# Arduino_Nano_Potentiometers.net
KiCad netlist of a schematic drawn in Altium Designer
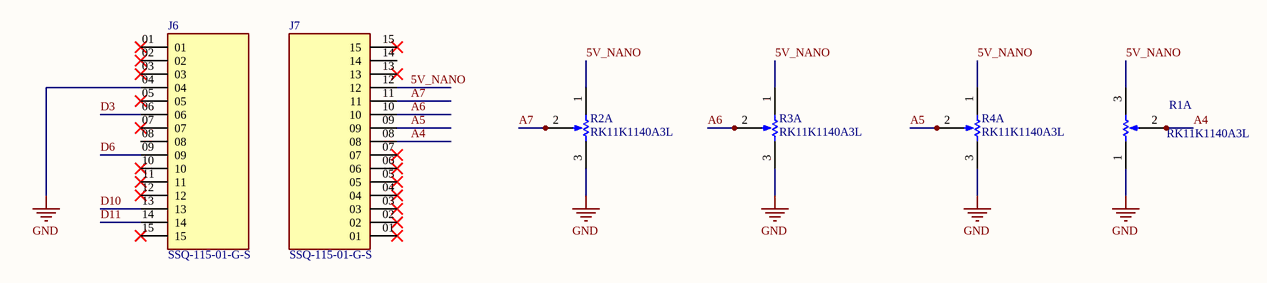
[diagram p0: Arduino_Nano + Potentiometers.schDoc]

(export (version "E")
  (design (tool "Eeschema 10.0.6"))
  (components
    (comp (ref "J6")
      (value "SSQ-115-01-G-S")
      (footprint "PcbLib1:SAMTEC_SSQ-115-01-G-S")
      (fields (field (name "MF") "Samtec"))
      (libsource (lib "") (part "SSQ-115-01-G-S_1"))
    )
    (comp (ref "J7")
      (value "SSQ-115-01-G-S")
      (footprint "PcbLib1:SAMTEC_SSQ-115-01-G-S")
      (fields (field (name "MF") "Samtec"))
      (libsource (lib "Schlib1") (part "SSQ-115-01-G-S"))
    )
    (comp (ref "R1")
      (value "RK11K1140A3L")
      (footprint "ALPS-RK11K1140A3L_V")
      (description "Rotary Potentiometer, 0.05 W, -10 to 70 degC, 4-Pin THD, RoHS")
      (fields (field (name "MANUFACTURER") "ALPS") (field (name "TOLERANCE") "20%"))
      (libsource (lib "") (part "CMP-2000-06982-1_1"))
    )
    (comp (ref "R2")
      (value "RK11K1140A3L")
      (footprint "ALPS-RK11K1140A3L_V")
      (description "Rotary Potentiometer, 0.05 W, -10 to 70 degC, 4-Pin THD, RoHS")
      (fields (field (name "MANUFACTURER") "ALPS") (field (name "TOLERANCE") "20%"))
      (libsource (lib "Schlib1") (part "CMP-2000-06982-1"))
    )
    (comp (ref "R3")
      (value "RK11K1140A3L")
      (footprint "ALPS-RK11K1140A3L_V")
      (description "Rotary Potentiometer, 0.05 W, -10 to 70 degC, 4-Pin THD, RoHS")
      (fields (field (name "MANUFACTURER") "ALPS") (field (name "TOLERANCE") "20%"))
      (libsource (lib "Schlib1") (part "CMP-2000-06982-1"))
    )
    (comp (ref "R4")
      (value "RK11K1140A3L")
      (footprint "ALPS-RK11K1140A3L_V")
      (description "Rotary Potentiometer, 0.05 W, -10 to 70 degC, 4-Pin THD, RoHS")
      (fields (field (name "MANUFACTURER") "ALPS") (field (name "TOLERANCE") "20%"))
      (libsource (lib "Schlib1") (part "CMP-2000-06982-1"))
    )
  )
  (nets
    (net (code "1") (name "/5V_NANO") (class "Default")
      (node (ref "J7") (pin "12") (pinfunction "12_12") (pintype "passive"))
      (node (ref "R1") (pin "3") (pinfunction "CW_3") (pintype "passive"))
      (node (ref "R2") (pin "1") (pinfunction "CCW_1") (pintype "passive"))
      (node (ref "R3") (pin "1") (pinfunction "CCW_1") (pintype "passive"))
      (node (ref "R4") (pin "1") (pinfunction "CCW_1") (pintype "passive"))
    )
    (net (code "2") (name "/A4") (class "Default")
      (node (ref "J7") (pin "08") (pinfunction "08_08") (pintype "passive"))
      (node (ref "R1") (pin "2") (pinfunction "WIPER_2") (pintype "passive"))
    )
    (net (code "3") (name "/A5") (class "Default")
      (node (ref "J7") (pin "09") (pinfunction "09_09") (pintype "passive"))
      (node (ref "R4") (pin "2") (pinfunction "WIPER_2") (pintype "passive"))
    )
    (net (code "4") (name "/A6") (class "Default")
      (node (ref "J7") (pin "10") (pinfunction "10_10") (pintype "passive"))
      (node (ref "R3") (pin "2") (pinfunction "WIPER_2") (pintype "passive"))
    )
    (net (code "5") (name "/A7") (class "Default")
      (node (ref "J7") (pin "11") (pinfunction "11_11") (pintype "passive"))
      (node (ref "R2") (pin "2") (pinfunction "WIPER_2") (pintype "passive"))
    )
    (net (code "6") (name "/D3") (class "Default")
      (node (ref "J6") (pin "06") (pinfunction "06_06") (pintype "passive"))
    )
    (net (code "7") (name "/D6") (class "Default")
      (node (ref "J6") (pin "09") (pinfunction "09_09") (pintype "passive"))
    )
    (net (code "8") (name "/D10") (class "Default")
      (node (ref "J6") (pin "13") (pinfunction "13_13") (pintype "passive"))
    )
    (net (code "9") (name "/D11") (class "Default")
      (node (ref "J6") (pin "14") (pinfunction "14_14") (pintype "passive"))
    )
    (net (code "10") (name "GND") (class "Default")
      (node (ref "J6") (pin "04") (pinfunction "04_04") (pintype "passive"))
      (node (ref "R1") (pin "1") (pinfunction "CCW_1") (pintype "passive"))
      (node (ref "R2") (pin "3") (pinfunction "CW_3") (pintype "passive"))
      (node (ref "R3") (pin "3") (pinfunction "CW_3") (pintype "passive"))
      (node (ref "R4") (pin "3") (pinfunction "CW_3") (pintype "passive"))
    )
    (net (code "11") (name "unconnected-(J6-Pad01)") (class "Default")
      (node (ref "J6") (pin "01") (pinfunction "01_01") (pintype "passive+no_connect"))
    )
    (net (code "12") (name "unconnected-(J6-Pad02)") (class "Default")
      (node (ref "J6") (pin "02") (pinfunction "02_02") (pintype "passive+no_connect"))
    )
    (net (code "13") (name "unconnected-(J6-Pad03)") (class "Default")
      (node (ref "J6") (pin "03") (pinfunction "03_03") (pintype "passive+no_connect"))
    )
    (net (code "14") (name "unconnected-(J6-Pad05)") (class "Default")
      (node (ref "J6") (pin "05") (pinfunction "05_05") (pintype "passive+no_connect"))
    )
    (net (code "15") (name "unconnected-(J6-Pad07)") (class "Default")
      (node (ref "J6") (pin "07") (pinfunction "07_07") (pintype "passive+no_connect"))
    )
    (net (code "16") (name "unconnected-(J6-Pad08)") (class "Default")
      (node (ref "J6") (pin "08") (pinfunction "08_08") (pintype "passive"))
    )
    (net (code "17") (name "unconnected-(J6-Pad10)") (class "Default")
      (node (ref "J6") (pin "10") (pinfunction "10_10") (pintype "passive+no_connect"))
    )
    (net (code "18") (name "unconnected-(J6-Pad11)") (class "Default")
      (node (ref "J6") (pin "11") (pinfunction "11_11") (pintype "passive+no_connect"))
    )
    (net (code "19") (name "unconnected-(J6-Pad12)") (class "Default")
      (node (ref "J6") (pin "12") (pinfunction "12_12") (pintype "passive+no_connect"))
    )
    (net (code "20") (name "unconnected-(J6-Pad15)") (class "Default")
      (node (ref "J6") (pin "15") (pinfunction "15_15") (pintype "passive+no_connect"))
    )
    (net (code "21") (name "unconnected-(J7-Pad01)") (class "Default")
      (node (ref "J7") (pin "01") (pinfunction "01_01") (pintype "passive+no_connect"))
    )
    (net (code "22") (name "unconnected-(J7-Pad02)") (class "Default")
      (node (ref "J7") (pin "02") (pinfunction "02_02") (pintype "passive+no_connect"))
    )
    (net (code "23") (name "unconnected-(J7-Pad03)") (class "Default")
      (node (ref "J7") (pin "03") (pinfunction "03_03") (pintype "passive+no_connect"))
    )
    (net (code "24") (name "unconnected-(J7-Pad04)") (class "Default")
      (node (ref "J7") (pin "04") (pinfunction "04_04") (pintype "passive+no_connect"))
    )
    (net (code "25") (name "unconnected-(J7-Pad05)") (class "Default")
      (node (ref "J7") (pin "05") (pinfunction "05_05") (pintype "passive+no_connect"))
    )
    (net (code "26") (name "unconnected-(J7-Pad06)") (class "Default")
      (node (ref "J7") (pin "06") (pinfunction "06_06") (pintype "passive+no_connect"))
    )
    (net (code "27") (name "unconnected-(J7-Pad07)") (class "Default")
      (node (ref "J7") (pin "07") (pinfunction "07_07") (pintype "passive+no_connect"))
    )
    (net (code "28") (name "unconnected-(J7-Pad13)") (class "Default")
      (node (ref "J7") (pin "13") (pinfunction "13_13") (pintype "passive+no_connect"))
    )
    (net (code "29") (name "unconnected-(J7-Pad14)") (class "Default")
      (node (ref "J7") (pin "14") (pinfunction "14_14") (pintype "passive"))
    )
    (net (code "30") (name "unconnected-(J7-Pad15)") (class "Default")
      (node (ref "J7") (pin "15") (pinfunction "15_15") (pintype "passive+no_connect"))
    )
  )
)
